# InterfaceBoardRevB.net
KiCad netlist of a schematic drawn in EAGLE
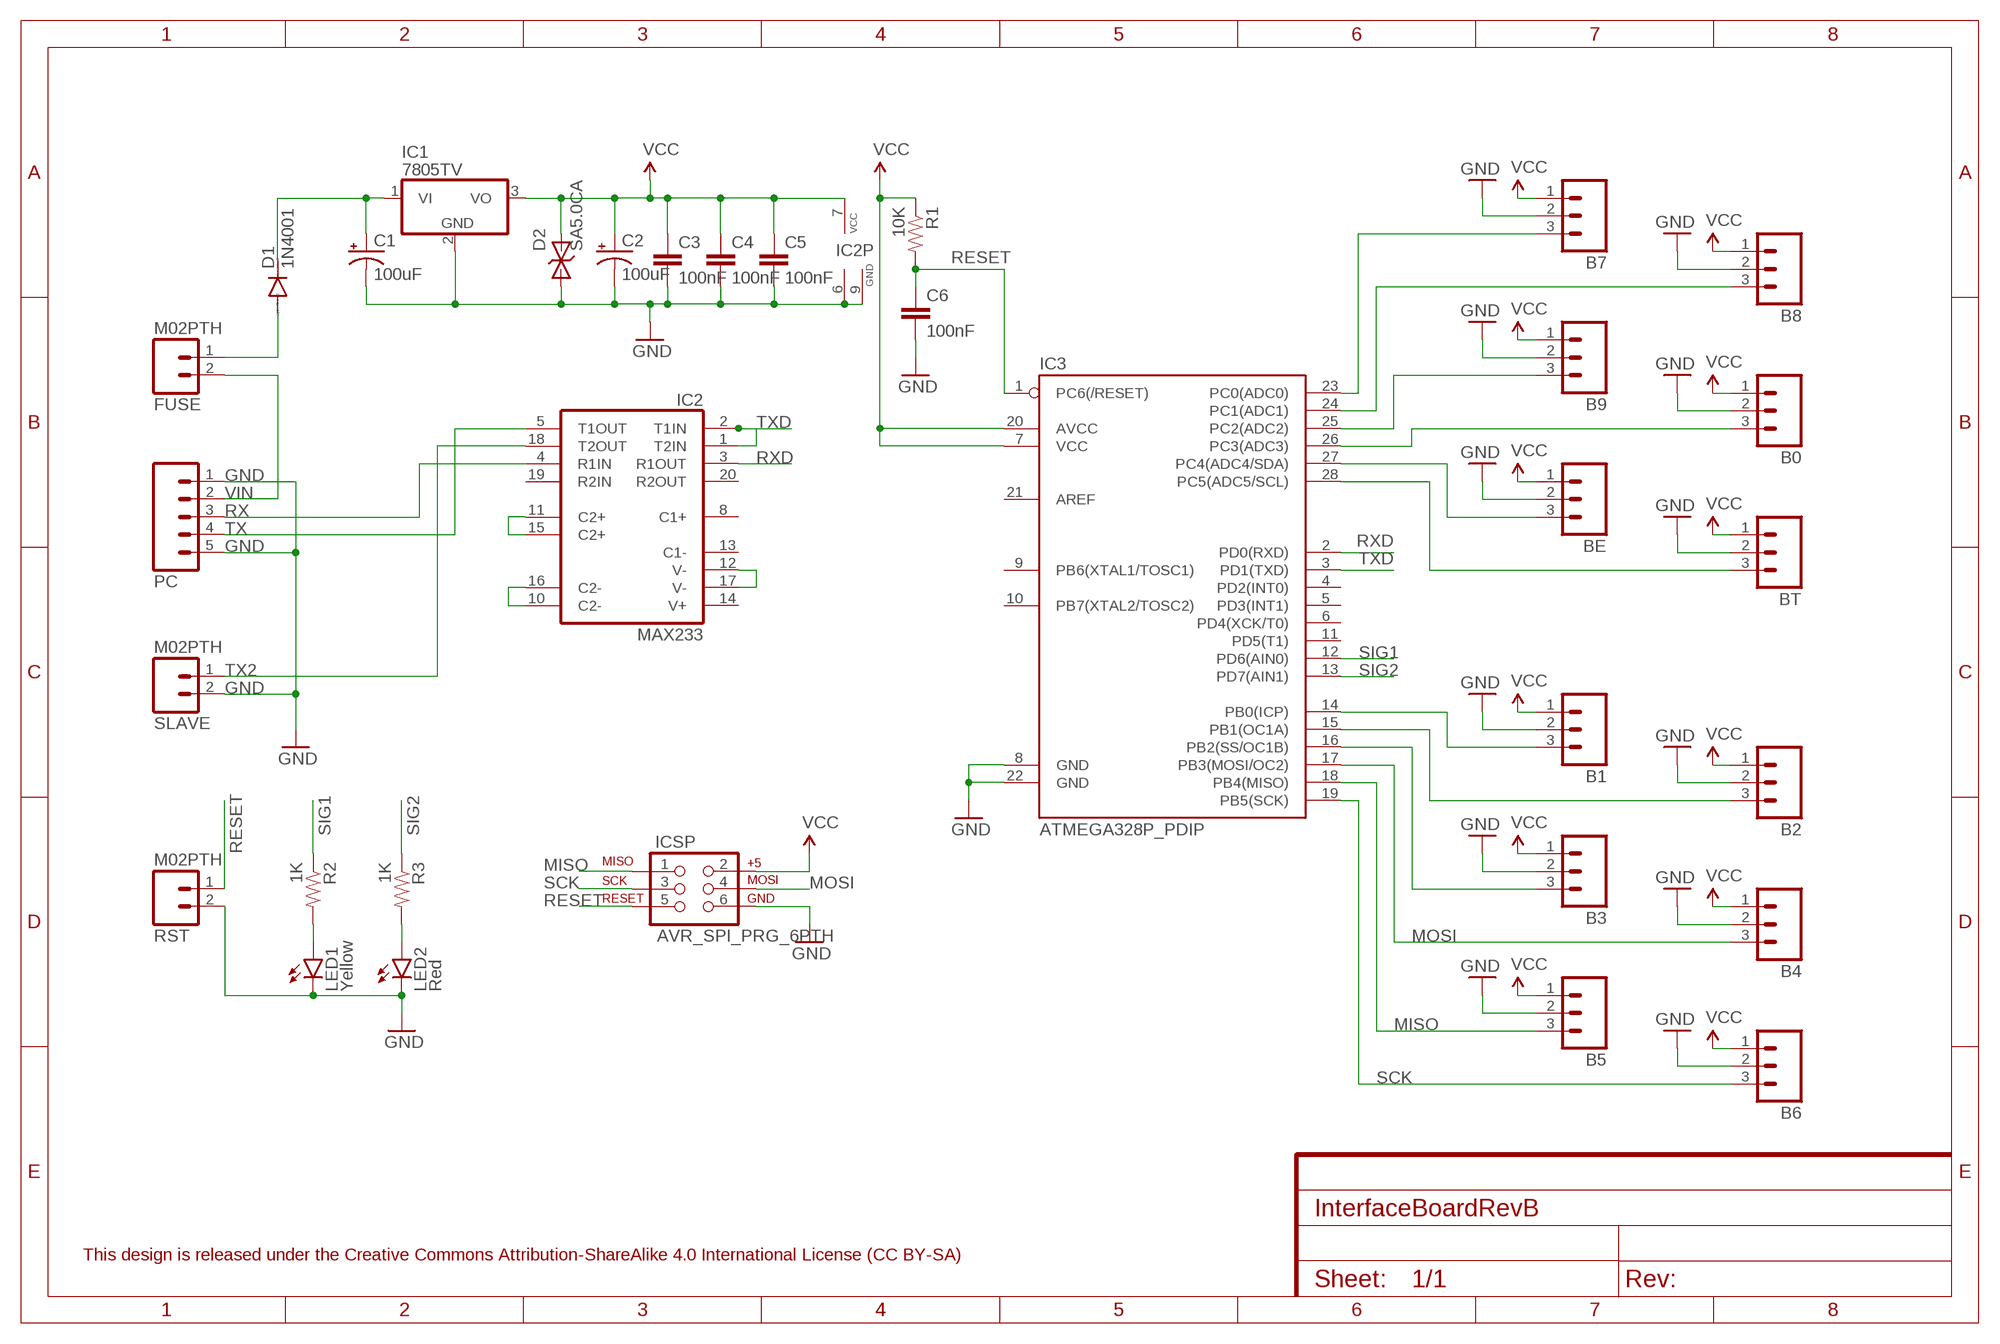
[diagram p0: schematic, sheet 1]

(export (version "E")
  (design (tool "Eeschema 10.0.6"))
  (components
    (comp (ref "B0")
      (value "M03PTH")
      (footprint "eagle-import:1X03")
      (libsource (lib "eagle-import") (part "M03PTH"))
    )
    (comp (ref "B1")
      (value "M03PTH")
      (footprint "eagle-import:1X03")
      (libsource (lib "eagle-import") (part "M03PTH"))
    )
    (comp (ref "B2")
      (value "M03PTH")
      (footprint "eagle-import:1X03")
      (libsource (lib "eagle-import") (part "M03PTH"))
    )
    (comp (ref "B3")
      (value "M03PTH")
      (footprint "eagle-import:1X03")
      (libsource (lib "eagle-import") (part "M03PTH"))
    )
    (comp (ref "B4")
      (value "M03PTH")
      (footprint "eagle-import:1X03")
      (libsource (lib "eagle-import") (part "M03PTH"))
    )
    (comp (ref "B5")
      (value "M03PTH")
      (footprint "eagle-import:1X03")
      (libsource (lib "eagle-import") (part "M03PTH"))
    )
    (comp (ref "B6")
      (value "M03PTH")
      (footprint "eagle-import:1X03")
      (libsource (lib "eagle-import") (part "M03PTH"))
    )
    (comp (ref "B7")
      (value "M03PTH")
      (footprint "eagle-import:1X03")
      (libsource (lib "eagle-import") (part "M03PTH"))
    )
    (comp (ref "B8")
      (value "M03PTH")
      (footprint "eagle-import:1X03")
      (libsource (lib "eagle-import") (part "M03PTH"))
    )
    (comp (ref "B9")
      (value "M03PTH")
      (footprint "eagle-import:1X03")
      (libsource (lib "eagle-import") (part "M03PTH"))
    )
    (comp (ref "BE")
      (value "M03PTH")
      (footprint "eagle-import:1X03")
      (libsource (lib "eagle-import") (part "M03PTH"))
    )
    (comp (ref "BT")
      (value "M03PTH")
      (footprint "eagle-import:1X03")
      (libsource (lib "eagle-import") (part "M03PTH"))
    )
    (comp (ref "C1")
      (value "100uF")
      (footprint "eagle-import:CPOL-RADIAL-100UF-25V")
      (libsource (lib "eagle-import") (part "CAP_POLPTH1"))
    )
    (comp (ref "C2")
      (value "100uF")
      (footprint "eagle-import:CPOL-RADIAL-100UF-25V")
      (libsource (lib "eagle-import") (part "CAP_POLPTH1"))
    )
    (comp (ref "C3")
      (value "100nF")
      (footprint "eagle-import:CAP-PTH-SMALL")
      (libsource (lib "eagle-import") (part "CAPPTH"))
    )
    (comp (ref "C4")
      (value "100nF")
      (footprint "eagle-import:CAP-PTH-SMALL")
      (libsource (lib "eagle-import") (part "CAPPTH"))
    )
    (comp (ref "C5")
      (value "100nF")
      (footprint "eagle-import:CAP-PTH-SMALL")
      (libsource (lib "eagle-import") (part "CAPPTH"))
    )
    (comp (ref "C6")
      (value "100nF")
      (footprint "eagle-import:CAP-PTH-SMALL")
      (libsource (lib "eagle-import") (part "CAPPTH"))
    )
    (comp (ref "D1")
      (value "1N4001")
      (footprint "eagle-import:DO41_DIODE")
      (libsource (lib "eagle-import") (part "1N4001"))
    )
    (comp (ref "D2")
      (value "SA5.0CA")
      (footprint "eagle-import:DO41_TVS")
      (libsource (lib "eagle-import") (part "SA5.0CA"))
    )
    (comp (ref "FUSE")
      (value "M02PTH")
      (footprint "eagle-import:1X02")
      (libsource (lib "eagle-import") (part "M02PTH"))
    )
    (comp (ref "IC1")
      (value "7805TV")
      (footprint "eagle-import:TO220V")
      (libsource (lib "eagle-import") (part "78TV05"))
    )
    (comp (ref "IC2")
      (value "MAX233")
      (footprint "eagle-import:DIL20")
      (fields (field (name "MPN") "MAX233ACPP+G36"))
      (libsource (lib "eagle-import") (part "MAX233"))
    )
    (comp (ref "IC3")
      (value "ATMEGA328P_PDIP")
      (footprint "eagle-import:DIL28-3")
      (libsource (lib "eagle-import") (part "ATMEGA328P_PDIP"))
    )
    (comp (ref "ICSP")
      (value "AVR_SPI_PRG_6PTH")
      (footprint "eagle-import:2X3")
      (libsource (lib "eagle-import") (part "AVR_SPI_PRG_6PTH"))
    )
    (comp (ref "LED1")
      (value "Yellow")
      (footprint "eagle-import:LED3MM_LARGEHOLES")
      (libsource (lib "eagle-import") (part "LED-LH3MM"))
    )
    (comp (ref "LED2")
      (value "Red")
      (footprint "eagle-import:LED3MM_LARGEHOLES")
      (libsource (lib "eagle-import") (part "LED-LH3MM"))
    )
    (comp (ref "PC")
      (value "M05PTH")
      (footprint "eagle-import:1X05")
      (libsource (lib "eagle-import") (part "M05PTH"))
    )
    (comp (ref "R1")
      (value "10K")
      (footprint "eagle-import:AXIAL-0.4")
      (libsource (lib "eagle-import") (part "RESISTORPTH-1/4W"))
    )
    (comp (ref "R2")
      (value "1K")
      (footprint "eagle-import:AXIAL-0.4")
      (libsource (lib "eagle-import") (part "RESISTORPTH-1/4W"))
    )
    (comp (ref "R3")
      (value "1K")
      (footprint "eagle-import:AXIAL-0.4")
      (libsource (lib "eagle-import") (part "RESISTORPTH-1/4W"))
    )
    (comp (ref "RST")
      (value "M02PTH")
      (footprint "eagle-import:1X02")
      (libsource (lib "eagle-import") (part "M02PTH"))
    )
    (comp (ref "SLAVE")
      (value "M02PTH")
      (footprint "eagle-import:1X02")
      (libsource (lib "eagle-import") (part "M02PTH"))
    )
  )
  (nets
    (net (code "1") (name "/MISO") (class "Default")
      (node (ref "B5") (pin "3") (pinfunction "3_3") (pintype "passive"))
      (node (ref "IC3") (pin "18") (pinfunction "PB4(MISO)_18") (pintype "bidirectional"))
      (node (ref "ICSP") (pin "1") (pinfunction "1_1") (pintype "passive"))
    )
    (net (code "2") (name "/MOSI") (class "Default")
      (node (ref "B4") (pin "3") (pinfunction "3_3") (pintype "passive"))
      (node (ref "IC3") (pin "17") (pinfunction "PB3(MOSI/OC2)_17") (pintype "bidirectional"))
      (node (ref "ICSP") (pin "4") (pinfunction "4_4") (pintype "passive"))
    )
    (net (code "3") (name "/RESET") (class "Default")
      (node (ref "C6") (pin "1") (pinfunction "1_1") (pintype "passive"))
      (node (ref "IC3") (pin "1") (pinfunction "PC6(/RESET)_1") (pintype "bidirectional"))
      (node (ref "ICSP") (pin "5") (pinfunction "5_5") (pintype "passive"))
      (node (ref "R1") (pin "P$2") (pinfunction "2_P$2") (pintype "passive"))
      (node (ref "RST") (pin "1") (pinfunction "1_1") (pintype "passive"))
    )
    (net (code "4") (name "/RX") (class "Default")
      (node (ref "IC2") (pin "4") (pinfunction "R1IN_4") (pintype "input"))
      (node (ref "PC") (pin "3") (pinfunction "3_3") (pintype "passive"))
    )
    (net (code "5") (name "/RXD") (class "Default")
      (node (ref "IC2") (pin "3") (pinfunction "R1OUT_3") (pintype "output"))
      (node (ref "IC3") (pin "2") (pinfunction "PD0(RXD)_2") (pintype "bidirectional"))
    )
    (net (code "6") (name "/SCK") (class "Default")
      (node (ref "B6") (pin "3") (pinfunction "3_3") (pintype "passive"))
      (node (ref "IC3") (pin "19") (pinfunction "PB5(SCK)_19") (pintype "bidirectional"))
      (node (ref "ICSP") (pin "3") (pinfunction "3_3") (pintype "passive"))
    )
    (net (code "7") (name "/SIG1") (class "Default")
      (node (ref "IC3") (pin "12") (pinfunction "PD6(AIN0)_12") (pintype "bidirectional"))
      (node (ref "R2") (pin "P$1") (pinfunction "1_P$1") (pintype "passive"))
    )
    (net (code "8") (name "/SIG2") (class "Default")
      (node (ref "IC3") (pin "13") (pinfunction "PD7(AIN1)_13") (pintype "bidirectional"))
      (node (ref "R3") (pin "P$1") (pinfunction "1_P$1") (pintype "passive"))
    )
    (net (code "9") (name "/TX") (class "Default")
      (node (ref "IC2") (pin "5") (pinfunction "T1OUT_5") (pintype "output"))
      (node (ref "PC") (pin "4") (pinfunction "4_4") (pintype "passive"))
    )
    (net (code "10") (name "/TX2") (class "Default")
      (node (ref "IC2") (pin "18") (pinfunction "T2OUT_18") (pintype "output"))
      (node (ref "SLAVE") (pin "1") (pinfunction "1_1") (pintype "passive"))
    )
    (net (code "11") (name "/TXD") (class "Default")
      (node (ref "IC2") (pin "1") (pinfunction "T2IN_1") (pintype "input"))
      (node (ref "IC2") (pin "2") (pinfunction "T1IN_2") (pintype "input"))
      (node (ref "IC3") (pin "3") (pinfunction "PD1(TXD)_3") (pintype "bidirectional"))
    )
    (net (code "12") (name "/VIN") (class "Default")
      (node (ref "FUSE") (pin "2") (pinfunction "2_2") (pintype "passive"))
      (node (ref "PC") (pin "2") (pinfunction "2_2") (pintype "passive"))
    )
    (net (code "13") (name "GND") (class "Default")
      (node (ref "B0") (pin "2") (pinfunction "2_2") (pintype "passive"))
      (node (ref "B1") (pin "2") (pinfunction "2_2") (pintype "passive"))
      (node (ref "B2") (pin "2") (pinfunction "2_2") (pintype "passive"))
      (node (ref "B3") (pin "2") (pinfunction "2_2") (pintype "passive"))
      (node (ref "B4") (pin "2") (pinfunction "2_2") (pintype "passive"))
      (node (ref "B5") (pin "2") (pinfunction "2_2") (pintype "passive"))
      (node (ref "B6") (pin "2") (pinfunction "2_2") (pintype "passive"))
      (node (ref "B7") (pin "2") (pinfunction "2_2") (pintype "passive"))
      (node (ref "B8") (pin "2") (pinfunction "2_2") (pintype "passive"))
      (node (ref "B9") (pin "2") (pinfunction "2_2") (pintype "passive"))
      (node (ref "BE") (pin "2") (pinfunction "2_2") (pintype "passive"))
      (node (ref "BT") (pin "2") (pinfunction "2_2") (pintype "passive"))
      (node (ref "C1") (pin "2") (pinfunction "-_2") (pintype "passive"))
      (node (ref "C2") (pin "2") (pinfunction "-_2") (pintype "passive"))
      (node (ref "C3") (pin "2") (pinfunction "2_2") (pintype "passive"))
      (node (ref "C4") (pin "2") (pinfunction "2_2") (pintype "passive"))
      (node (ref "C5") (pin "2") (pinfunction "2_2") (pintype "passive"))
      (node (ref "C6") (pin "2") (pinfunction "2_2") (pintype "passive"))
      (node (ref "D2") (pin "A") (pinfunction "A_A") (pintype "passive"))
      (node (ref "IC1") (pin "2") (pinfunction "GND_2") (pintype "passive"))
      (node (ref "IC2") (pin "6") (pinfunction "GND_6") (pintype "power_in"))
      (node (ref "IC2") (pin "9") (pinfunction "GND_9") (pintype "power_in"))
      (node (ref "IC3") (pin "22") (pinfunction "GND_22") (pintype "bidirectional"))
      (node (ref "IC3") (pin "8") (pinfunction "GND_8") (pintype "bidirectional"))
      (node (ref "ICSP") (pin "6") (pinfunction "6_6") (pintype "passive"))
      (node (ref "LED1") (pin "K") (pinfunction "C_K") (pintype "passive"))
      (node (ref "LED2") (pin "K") (pinfunction "C_K") (pintype "passive"))
      (node (ref "PC") (pin "1") (pinfunction "1_1") (pintype "passive"))
      (node (ref "PC") (pin "5") (pinfunction "5_5") (pintype "passive"))
      (node (ref "RST") (pin "2") (pinfunction "2_2") (pintype "passive"))
      (node (ref "SLAVE") (pin "2") (pinfunction "2_2") (pintype "passive"))
    )
    (net (code "14") (name "Net-(C1-+)") (class "Default")
      (node (ref "C1") (pin "1") (pinfunction "+_1") (pintype "passive"))
      (node (ref "D1") (pin "C") (pinfunction "C_C") (pintype "passive"))
      (node (ref "IC1") (pin "1") (pinfunction "VI_1") (pintype "input"))
    )
    (net (code "15") (name "Net-(D1-PadA)") (class "Default")
      (node (ref "D1") (pin "A") (pinfunction "A_A") (pintype "passive"))
      (node (ref "FUSE") (pin "1") (pinfunction "1_1") (pintype "passive"))
    )
    (net (code "16") (name "Net-(IC2A-C2+-Pad11)") (class "Default")
      (node (ref "IC2") (pin "11") (pinfunction "C2+_11") (pintype "bidirectional"))
      (node (ref "IC2") (pin "15") (pinfunction "C2+_15") (pintype "bidirectional"))
    )
    (net (code "17") (name "Net-(IC2A-C2--Pad10)") (class "Default")
      (node (ref "IC2") (pin "10") (pinfunction "C2-_10") (pintype "bidirectional"))
      (node (ref "IC2") (pin "16") (pinfunction "C2-_16") (pintype "bidirectional"))
    )
    (net (code "18") (name "Net-(IC2A-V--Pad12)") (class "Default")
      (node (ref "IC2") (pin "12") (pinfunction "V-_12") (pintype "bidirectional"))
      (node (ref "IC2") (pin "17") (pinfunction "V-_17") (pintype "bidirectional"))
    )
    (net (code "19") (name "Net-(IC3-PB0(ICP))") (class "Default")
      (node (ref "B1") (pin "3") (pinfunction "3_3") (pintype "passive"))
      (node (ref "IC3") (pin "14") (pinfunction "PB0(ICP)_14") (pintype "bidirectional"))
    )
    (net (code "20") (name "Net-(IC3-PB1(OC1A))") (class "Default")
      (node (ref "B2") (pin "3") (pinfunction "3_3") (pintype "passive"))
      (node (ref "IC3") (pin "15") (pinfunction "PB1(OC1A)_15") (pintype "bidirectional"))
    )
    (net (code "21") (name "Net-(IC3-PB2(SS{slash}OC1B))") (class "Default")
      (node (ref "B3") (pin "3") (pinfunction "3_3") (pintype "passive"))
      (node (ref "IC3") (pin "16") (pinfunction "PB2(SS/OC1B)_16") (pintype "bidirectional"))
    )
    (net (code "22") (name "Net-(IC3-PC0(ADC0))") (class "Default")
      (node (ref "B7") (pin "3") (pinfunction "3_3") (pintype "passive"))
      (node (ref "IC3") (pin "23") (pinfunction "PC0(ADC0)_23") (pintype "bidirectional"))
    )
    (net (code "23") (name "Net-(IC3-PC1(ADC1))") (class "Default")
      (node (ref "B8") (pin "3") (pinfunction "3_3") (pintype "passive"))
      (node (ref "IC3") (pin "24") (pinfunction "PC1(ADC1)_24") (pintype "bidirectional"))
    )
    (net (code "24") (name "Net-(IC3-PC2(ADC2))") (class "Default")
      (node (ref "B9") (pin "3") (pinfunction "3_3") (pintype "passive"))
      (node (ref "IC3") (pin "25") (pinfunction "PC2(ADC2)_25") (pintype "bidirectional"))
    )
    (net (code "25") (name "Net-(IC3-PC3(ADC3))") (class "Default")
      (node (ref "B0") (pin "3") (pinfunction "3_3") (pintype "passive"))
      (node (ref "IC3") (pin "26") (pinfunction "PC3(ADC3)_26") (pintype "bidirectional"))
    )
    (net (code "26") (name "Net-(IC3-PC4(ADC4{slash}SDA))") (class "Default")
      (node (ref "BE") (pin "3") (pinfunction "3_3") (pintype "passive"))
      (node (ref "IC3") (pin "27") (pinfunction "PC4(ADC4/SDA)_27") (pintype "bidirectional"))
    )
    (net (code "27") (name "Net-(IC3-PC5(ADC5{slash}SCL))") (class "Default")
      (node (ref "BT") (pin "3") (pinfunction "3_3") (pintype "passive"))
      (node (ref "IC3") (pin "28") (pinfunction "PC5(ADC5/SCL)_28") (pintype "bidirectional"))
    )
    (net (code "28") (name "Net-(R2-2)") (class "Default")
      (node (ref "LED1") (pin "A") (pinfunction "A_A") (pintype "passive"))
      (node (ref "R2") (pin "P$2") (pinfunction "2_P$2") (pintype "passive"))
    )
    (net (code "29") (name "Net-(R3-2)") (class "Default")
      (node (ref "LED2") (pin "A") (pinfunction "A_A") (pintype "passive"))
      (node (ref "R3") (pin "P$2") (pinfunction "2_P$2") (pintype "passive"))
    )
    (net (code "30") (name "VCC") (class "Default")
      (node (ref "B0") (pin "1") (pinfunction "1_1") (pintype "passive"))
      (node (ref "B1") (pin "1") (pinfunction "1_1") (pintype "passive"))
      (node (ref "B2") (pin "1") (pinfunction "1_1") (pintype "passive"))
      (node (ref "B3") (pin "1") (pinfunction "1_1") (pintype "passive"))
      (node (ref "B4") (pin "1") (pinfunction "1_1") (pintype "passive"))
      (node (ref "B5") (pin "1") (pinfunction "1_1") (pintype "passive"))
      (node (ref "B6") (pin "1") (pinfunction "1_1") (pintype "passive"))
      (node (ref "B7") (pin "1") (pinfunction "1_1") (pintype "passive"))
      (node (ref "B8") (pin "1") (pinfunction "1_1") (pintype "passive"))
      (node (ref "B9") (pin "1") (pinfunction "1_1") (pintype "passive"))
      (node (ref "BE") (pin "1") (pinfunction "1_1") (pintype "passive"))
      (node (ref "BT") (pin "1") (pinfunction "1_1") (pintype "passive"))
      (node (ref "C2") (pin "1") (pinfunction "+_1") (pintype "passive"))
      (node (ref "C3") (pin "1") (pinfunction "1_1") (pintype "passive"))
      (node (ref "C4") (pin "1") (pinfunction "1_1") (pintype "passive"))
      (node (ref "C5") (pin "1") (pinfunction "1_1") (pintype "passive"))
      (node (ref "D2") (pin "C") (pinfunction "C_C") (pintype "passive"))
      (node (ref "IC1") (pin "3") (pinfunction "VO_3") (pintype "passive"))
      (node (ref "IC2") (pin "7") (pinfunction "VCC_7") (pintype "power_in"))
      (node (ref "IC3") (pin "20") (pinfunction "AVCC_20") (pintype "bidirectional"))
      (node (ref "IC3") (pin "7") (pinfunction "VCC_7") (pintype "bidirectional"))
      (node (ref "ICSP") (pin "2") (pinfunction "2_2") (pintype "passive"))
      (node (ref "R1") (pin "P$1") (pinfunction "1_P$1") (pintype "passive"))
    )
    (net (code "31") (name "unconnected-(IC2A-C1+-Pad8)") (class "Default")
      (node (ref "IC2") (pin "8") (pinfunction "C1+_8") (pintype "bidirectional"))
    )
    (net (code "32") (name "unconnected-(IC2A-C1--Pad13)") (class "Default")
      (node (ref "IC2") (pin "13") (pinfunction "C1-_13") (pintype "bidirectional"))
    )
    (net (code "33") (name "unconnected-(IC2A-R2IN-Pad19)") (class "Default")
      (node (ref "IC2") (pin "19") (pinfunction "R2IN_19") (pintype "input"))
    )
    (net (code "34") (name "unconnected-(IC2A-R2OUT-Pad20)") (class "Default")
      (node (ref "IC2") (pin "20") (pinfunction "R2OUT_20") (pintype "output"))
    )
    (net (code "35") (name "unconnected-(IC2A-V+-Pad14)") (class "Default")
      (node (ref "IC2") (pin "14") (pinfunction "V+_14") (pintype "bidirectional"))
    )
    (net (code "36") (name "unconnected-(IC3-AREF-Pad21)") (class "Default")
      (node (ref "IC3") (pin "21") (pinfunction "AREF_21") (pintype "bidirectional"))
    )
    (net (code "37") (name "unconnected-(IC3-PB6(XTAL1{slash}TOSC1)-Pad9)") (class "Default")
      (node (ref "IC3") (pin "9") (pinfunction "PB6(XTAL1/TOSC1)_9") (pintype "bidirectional"))
    )
    (net (code "38") (name "unconnected-(IC3-PB7(XTAL2{slash}TOSC2)-Pad10)") (class "Default")
      (node (ref "IC3") (pin "10") (pinfunction "PB7(XTAL2/TOSC2)_10") (pintype "bidirectional"))
    )
    (net (code "39") (name "unconnected-(IC3-PD2(INT0)-Pad4)") (class "Default")
      (node (ref "IC3") (pin "4") (pinfunction "PD2(INT0)_4") (pintype "bidirectional"))
    )
    (net (code "40") (name "unconnected-(IC3-PD3(INT1)-Pad5)") (class "Default")
      (node (ref "IC3") (pin "5") (pinfunction "PD3(INT1)_5") (pintype "bidirectional"))
    )
    (net (code "41") (name "unconnected-(IC3-PD4(XCK{slash}T0)-Pad6)") (class "Default")
      (node (ref "IC3") (pin "6") (pinfunction "PD4(XCK/T0)_6") (pintype "bidirectional"))
    )
    (net (code "42") (name "unconnected-(IC3-PD5(T1)-Pad11)") (class "Default")
      (node (ref "IC3") (pin "11") (pinfunction "PD5(T1)_11") (pintype "bidirectional"))
    )
  )
)
